# Microcontroller_sch_v22_2.net
KiCad netlist of a schematic drawn in Altium Designer
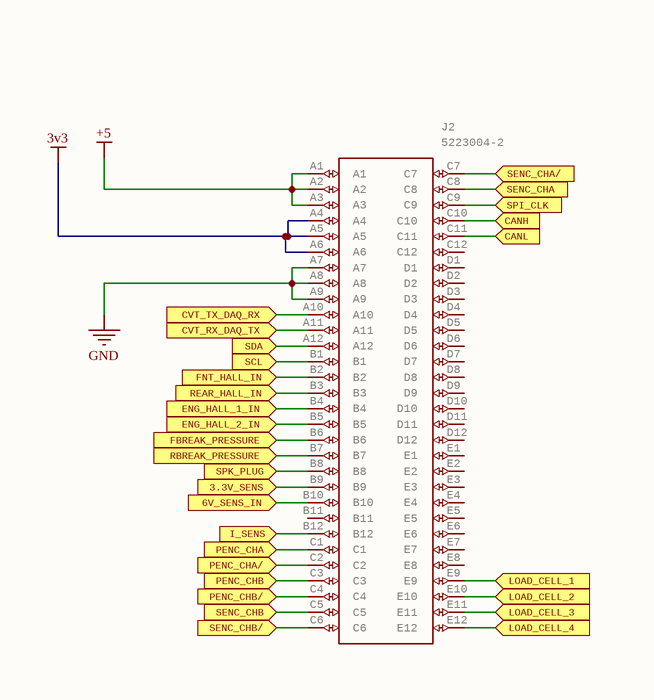
[diagram p0: Microcontroller_sch_v22_2.SchDoc]

(export (version "E")
  (design (tool "Eeschema 10.0.6"))
  (components
    (comp (ref "J2")
      (value "5223004-2")
      (footprint "52230042")
      (description "Conn Backplane RCP 60 POS 2mm Solder RA Thru-Hole Tube   Source:  Datasheet")
      (fields (field (name "MOUSER_PART_NUMBER") "571-5223004-2"))
      (libsource (lib "SamacSys_Parts") (part "5223004-2"))
    )
  )
  (nets
    (net (code "1") (name "+5") (class "Default")
      (node (ref "J2") (pin "A1") (pinfunction "A1_A1") (pintype "bidirectional"))
      (node (ref "J2") (pin "A2") (pinfunction "A2_A2") (pintype "bidirectional"))
      (node (ref "J2") (pin "A3") (pinfunction "A3_A3") (pintype "bidirectional"))
    )
    (net (code "2") (name "/3.3V_SENS") (class "Default")
      (node (ref "J2") (pin "B9") (pinfunction "B9_B9") (pintype "bidirectional"))
    )
    (net (code "3") (name "/6V_SENS_IN") (class "Default")
      (node (ref "J2") (pin "B10") (pinfunction "B10_B10") (pintype "bidirectional"))
    )
    (net (code "4") (name "/CANH") (class "Default")
      (node (ref "J2") (pin "C10") (pinfunction "C10_C10") (pintype "bidirectional"))
    )
    (net (code "5") (name "/CANL") (class "Default")
      (node (ref "J2") (pin "C11") (pinfunction "C11_C11") (pintype "bidirectional"))
    )
    (net (code "6") (name "/CVT_RX_DAQ_TX") (class "Default")
      (node (ref "J2") (pin "A11") (pinfunction "A11_A11") (pintype "bidirectional"))
    )
    (net (code "7") (name "/CVT_TX_DAQ_RX") (class "Default")
      (node (ref "J2") (pin "A10") (pinfunction "A10_A10") (pintype "bidirectional"))
    )
    (net (code "8") (name "/ENG_HALL_1_IN") (class "Default")
      (node (ref "J2") (pin "B4") (pinfunction "B4_B4") (pintype "bidirectional"))
    )
    (net (code "9") (name "/ENG_HALL_2_IN") (class "Default")
      (node (ref "J2") (pin "B5") (pinfunction "B5_B5") (pintype "bidirectional"))
    )
    (net (code "10") (name "/FBREAK_PRESSURE") (class "Default")
      (node (ref "J2") (pin "B6") (pinfunction "B6_B6") (pintype "bidirectional"))
    )
    (net (code "11") (name "/FNT_HALL_IN") (class "Default")
      (node (ref "J2") (pin "B2") (pinfunction "B2_B2") (pintype "bidirectional"))
    )
    (net (code "12") (name "/I_SENS") (class "Default")
      (node (ref "J2") (pin "B12") (pinfunction "B12_B12") (pintype "bidirectional"))
    )
    (net (code "13") (name "/LOAD_CELL_1") (class "Default")
      (node (ref "J2") (pin "E9") (pinfunction "E9_E9") (pintype "bidirectional"))
    )
    (net (code "14") (name "/LOAD_CELL_2") (class "Default")
      (node (ref "J2") (pin "E10") (pinfunction "E10_E10") (pintype "bidirectional"))
    )
    (net (code "15") (name "/LOAD_CELL_3") (class "Default")
      (node (ref "J2") (pin "E11") (pinfunction "E11_E11") (pintype "bidirectional"))
    )
    (net (code "16") (name "/LOAD_CELL_4") (class "Default")
      (node (ref "J2") (pin "E12") (pinfunction "E12_E12") (pintype "bidirectional"))
    )
    (net (code "17") (name "/PENC_CHA") (class "Default")
      (node (ref "J2") (pin "C1") (pinfunction "C1_C1") (pintype "bidirectional"))
    )
    (net (code "18") (name "/PENC_CHA{slash}") (class "Default")
      (node (ref "J2") (pin "C2") (pinfunction "C2_C2") (pintype "bidirectional"))
    )
    (net (code "19") (name "/PENC_CHB") (class "Default")
      (node (ref "J2") (pin "C3") (pinfunction "C3_C3") (pintype "bidirectional"))
    )
    (net (code "20") (name "/PENC_CHB{slash}") (class "Default")
      (node (ref "J2") (pin "C4") (pinfunction "C4_C4") (pintype "bidirectional"))
    )
    (net (code "21") (name "/RBREAK_PRESSURE") (class "Default")
      (node (ref "J2") (pin "B7") (pinfunction "B7_B7") (pintype "bidirectional"))
    )
    (net (code "22") (name "/REAR_HALL_IN") (class "Default")
      (node (ref "J2") (pin "B3") (pinfunction "B3_B3") (pintype "bidirectional"))
    )
    (net (code "23") (name "/SCL") (class "Default")
      (node (ref "J2") (pin "B1") (pinfunction "B1_B1") (pintype "bidirectional"))
    )
    (net (code "24") (name "/SDA") (class "Default")
      (node (ref "J2") (pin "A12") (pinfunction "A12_A12") (pintype "bidirectional"))
    )
    (net (code "25") (name "/SENC_CHA") (class "Default")
      (node (ref "J2") (pin "C8") (pinfunction "C8_C8") (pintype "bidirectional"))
    )
    (net (code "26") (name "/SENC_CHA{slash}") (class "Default")
      (node (ref "J2") (pin "C7") (pinfunction "C7_C7") (pintype "bidirectional"))
    )
    (net (code "27") (name "/SENC_CHB") (class "Default")
      (node (ref "J2") (pin "C5") (pinfunction "C5_C5") (pintype "bidirectional"))
    )
    (net (code "28") (name "/SENC_CHB{slash}") (class "Default")
      (node (ref "J2") (pin "C6") (pinfunction "C6_C6") (pintype "bidirectional"))
    )
    (net (code "29") (name "/SPI_CLK") (class "Default")
      (node (ref "J2") (pin "C9") (pinfunction "C9_C9") (pintype "bidirectional"))
    )
    (net (code "30") (name "/SPK_PLUG") (class "Default")
      (node (ref "J2") (pin "B8") (pinfunction "B8_B8") (pintype "bidirectional"))
    )
    (net (code "31") (name "3v3") (class "Default")
      (node (ref "J2") (pin "A4") (pinfunction "A4_A4") (pintype "bidirectional"))
      (node (ref "J2") (pin "A5") (pinfunction "A5_A5") (pintype "bidirectional"))
      (node (ref "J2") (pin "A6") (pinfunction "A6_A6") (pintype "bidirectional"))
    )
    (net (code "32") (name "GND") (class "Default")
      (node (ref "J2") (pin "A7") (pinfunction "A7_A7") (pintype "bidirectional"))
      (node (ref "J2") (pin "A8") (pinfunction "A8_A8") (pintype "bidirectional"))
      (node (ref "J2") (pin "A9") (pinfunction "A9_A9") (pintype "bidirectional"))
    )
    (net (code "33") (name "unconnected-(J2-PadB11)") (class "Default")
      (node (ref "J2") (pin "B11") (pinfunction "B11_B11") (pintype "bidirectional"))
    )
    (net (code "34") (name "unconnected-(J2-PadC12)") (class "Default")
      (node (ref "J2") (pin "C12") (pinfunction "C12_C12") (pintype "bidirectional"))
    )
    (net (code "35") (name "unconnected-(J2-PadD1)") (class "Default")
      (node (ref "J2") (pin "D1") (pinfunction "D1_D1") (pintype "bidirectional"))
    )
    (net (code "36") (name "unconnected-(J2-PadD2)") (class "Default")
      (node (ref "J2") (pin "D2") (pinfunction "D2_D2") (pintype "bidirectional"))
    )
    (net (code "37") (name "unconnected-(J2-PadD3)") (class "Default")
      (node (ref "J2") (pin "D3") (pinfunction "D3_D3") (pintype "bidirectional"))
    )
    (net (code "38") (name "unconnected-(J2-PadD4)") (class "Default")
      (node (ref "J2") (pin "D4") (pinfunction "D4_D4") (pintype "bidirectional"))
    )
    (net (code "39") (name "unconnected-(J2-PadD5)") (class "Default")
      (node (ref "J2") (pin "D5") (pinfunction "D5_D5") (pintype "bidirectional"))
    )
    (net (code "40") (name "unconnected-(J2-PadD6)") (class "Default")
      (node (ref "J2") (pin "D6") (pinfunction "D6_D6") (pintype "bidirectional"))
    )
    (net (code "41") (name "unconnected-(J2-PadD7)") (class "Default")
      (node (ref "J2") (pin "D7") (pinfunction "D7_D7") (pintype "bidirectional"))
    )
    (net (code "42") (name "unconnected-(J2-PadD8)") (class "Default")
      (node (ref "J2") (pin "D8") (pinfunction "D8_D8") (pintype "bidirectional"))
    )
    (net (code "43") (name "unconnected-(J2-PadD9)") (class "Default")
      (node (ref "J2") (pin "D9") (pinfunction "D9_D9") (pintype "bidirectional"))
    )
    (net (code "44") (name "unconnected-(J2-PadD10)") (class "Default")
      (node (ref "J2") (pin "D10") (pinfunction "D10_D10") (pintype "bidirectional"))
    )
    (net (code "45") (name "unconnected-(J2-PadD11)") (class "Default")
      (node (ref "J2") (pin "D11") (pinfunction "D11_D11") (pintype "bidirectional"))
    )
    (net (code "46") (name "unconnected-(J2-PadD12)") (class "Default")
      (node (ref "J2") (pin "D12") (pinfunction "D12_D12") (pintype "bidirectional"))
    )
    (net (code "47") (name "unconnected-(J2-PadE1)") (class "Default")
      (node (ref "J2") (pin "E1") (pinfunction "E1_E1") (pintype "bidirectional"))
    )
    (net (code "48") (name "unconnected-(J2-PadE2)") (class "Default")
      (node (ref "J2") (pin "E2") (pinfunction "E2_E2") (pintype "bidirectional"))
    )
    (net (code "49") (name "unconnected-(J2-PadE3)") (class "Default")
      (node (ref "J2") (pin "E3") (pinfunction "E3_E3") (pintype "bidirectional"))
    )
    (net (code "50") (name "unconnected-(J2-PadE4)") (class "Default")
      (node (ref "J2") (pin "E4") (pinfunction "E4_E4") (pintype "bidirectional"))
    )
    (net (code "51") (name "unconnected-(J2-PadE5)") (class "Default")
      (node (ref "J2") (pin "E5") (pinfunction "E5_E5") (pintype "bidirectional"))
    )
    (net (code "52") (name "unconnected-(J2-PadE6)") (class "Default")
      (node (ref "J2") (pin "E6") (pinfunction "E6_E6") (pintype "bidirectional"))
    )
    (net (code "53") (name "unconnected-(J2-PadE7)") (class "Default")
      (node (ref "J2") (pin "E7") (pinfunction "E7_E7") (pintype "bidirectional"))
    )
    (net (code "54") (name "unconnected-(J2-PadE8)") (class "Default")
      (node (ref "J2") (pin "E8") (pinfunction "E8_E8") (pintype "bidirectional"))
    )
  )
)
